# artlight_cornhole.net
KiCad netlist of a schematic drawn in EAGLE
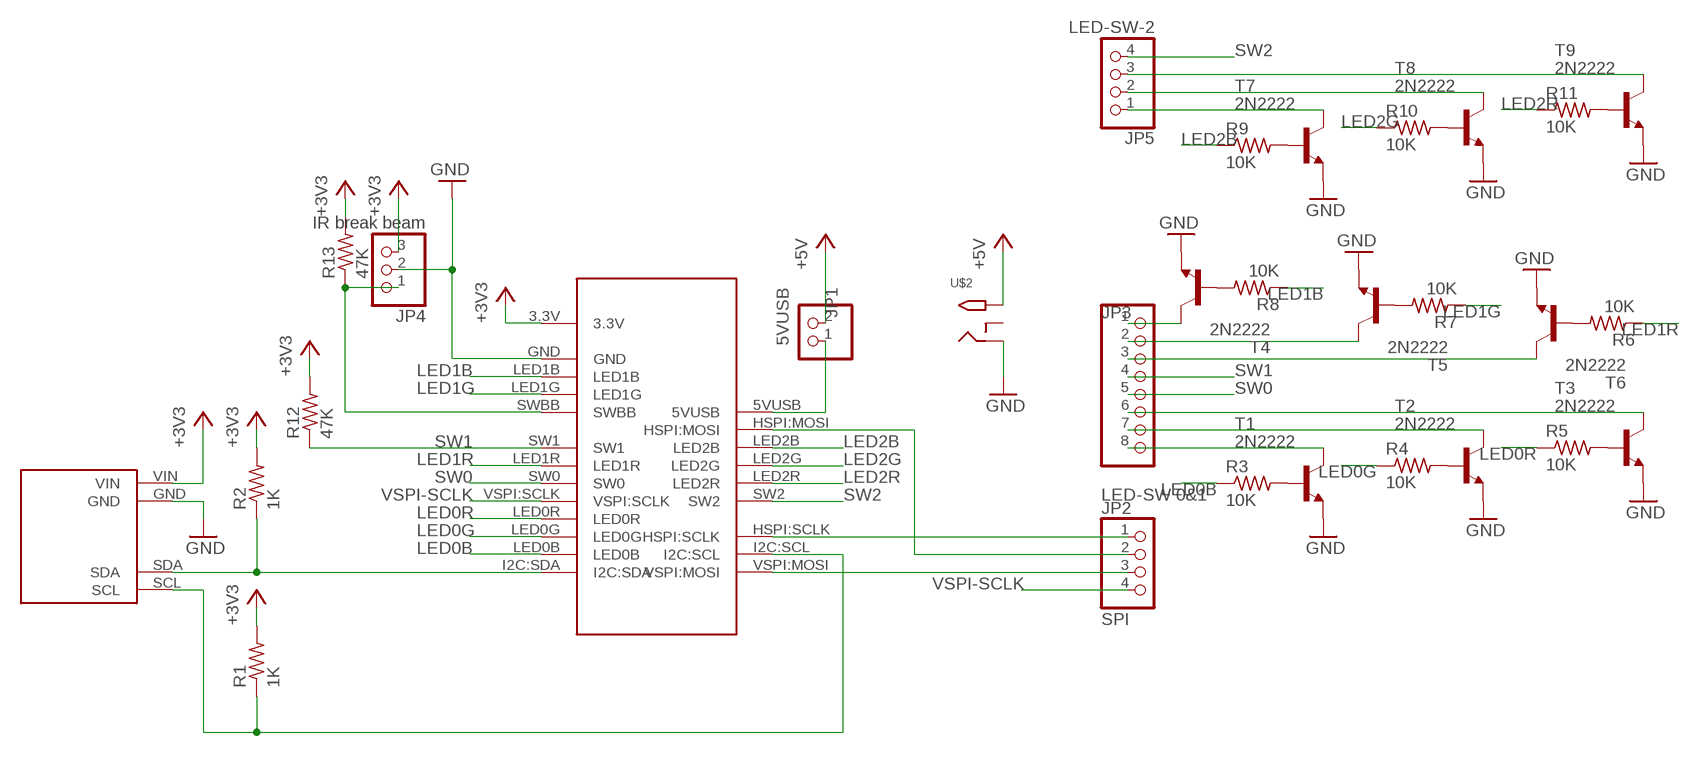
[diagram p0: schematic, sheet 1]

(export (version "E")
  (design (tool "Eeschema 10.0.6"))
  (components
    (comp (ref "JP1")
      (value "5VUSB")
      (footprint "eagle-import:1X02")
      (libsource (lib "eagle-import") (part "PINHD-1X2"))
    )
    (comp (ref "JP2")
      (value "SPI")
      (footprint "eagle-import:1X04")
      (libsource (lib "eagle-import") (part "PINHD-1X4"))
    )
    (comp (ref "JP3")
      (value "LED-SW 0&1")
      (footprint "eagle-import:1X08")
      (libsource (lib "eagle-import") (part "PINHD-1X8"))
    )
    (comp (ref "JP4")
      (value "IR break beam")
      (footprint "eagle-import:1X03")
      (libsource (lib "eagle-import") (part "PINHD-1X3"))
    )
    (comp (ref "JP5")
      (value "LED-SW-2")
      (footprint "eagle-import:1X04")
      (libsource (lib "eagle-import") (part "PINHD-1X4"))
    )
    (comp (ref "R1")
      (value "1K")
      (footprint "eagle-import:0204_7")
      (libsource (lib "eagle-import") (part "R-US_0204/7"))
    )
    (comp (ref "R2")
      (value "1K")
      (footprint "eagle-import:0204_7")
      (libsource (lib "eagle-import") (part "R-US_0204/7"))
    )
    (comp (ref "R3")
      (value "10K")
      (footprint "eagle-import:0204V")
      (libsource (lib "eagle-import") (part "R-US_0204/2V"))
    )
    (comp (ref "R4")
      (value "10K")
      (footprint "eagle-import:0204V")
      (libsource (lib "eagle-import") (part "R-US_0204/2V"))
    )
    (comp (ref "R5")
      (value "10K")
      (footprint "eagle-import:0204V")
      (libsource (lib "eagle-import") (part "R-US_0204/2V"))
    )
    (comp (ref "R6")
      (value "10K")
      (footprint "eagle-import:0204V")
      (libsource (lib "eagle-import") (part "R-US_0204/2V"))
    )
    (comp (ref "R7")
      (value "10K")
      (footprint "eagle-import:0204V")
      (libsource (lib "eagle-import") (part "R-US_0204/2V"))
    )
    (comp (ref "R8")
      (value "10K")
      (footprint "eagle-import:0204V")
      (libsource (lib "eagle-import") (part "R-US_0204/2V"))
    )
    (comp (ref "R9")
      (value "10K")
      (footprint "eagle-import:0204V")
      (libsource (lib "eagle-import") (part "R-US_0204/2V"))
    )
    (comp (ref "R10")
      (value "10K")
      (footprint "eagle-import:0204V")
      (libsource (lib "eagle-import") (part "R-US_0204/2V"))
    )
    (comp (ref "R11")
      (value "10K")
      (footprint "eagle-import:0204V")
      (libsource (lib "eagle-import") (part "R-US_0204/2V"))
    )
    (comp (ref "R12")
      (value "47K")
      (footprint "eagle-import:0204_7")
      (libsource (lib "eagle-import") (part "R-US_0204/7"))
    )
    (comp (ref "R13")
      (value "47K")
      (footprint "eagle-import:0204_7")
      (libsource (lib "eagle-import") (part "R-US_0204/7"))
    )
    (comp (ref "T1")
      (value "2N2222")
      (footprint "eagle-import:TO92-EBC-OVAL")
      (libsource (lib "eagle-import") (part "2N2222"))
    )
    (comp (ref "T2")
      (value "2N2222")
      (footprint "eagle-import:TO92-EBC-OVAL")
      (libsource (lib "eagle-import") (part "2N2222"))
    )
    (comp (ref "T3")
      (value "2N2222")
      (footprint "eagle-import:TO92-EBC-OVAL")
      (libsource (lib "eagle-import") (part "2N2222"))
    )
    (comp (ref "T4")
      (value "2N2222")
      (footprint "eagle-import:TO92-EBC-OVAL")
      (libsource (lib "eagle-import") (part "2N2222"))
    )
    (comp (ref "T5")
      (value "2N2222")
      (footprint "eagle-import:TO92-EBC-OVAL")
      (libsource (lib "eagle-import") (part "2N2222"))
    )
    (comp (ref "T6")
      (value "2N2222")
      (footprint "eagle-import:TO92-EBC-OVAL")
      (libsource (lib "eagle-import") (part "2N2222"))
    )
    (comp (ref "T7")
      (value "2N2222")
      (footprint "eagle-import:TO92-EBC-OVAL")
      (libsource (lib "eagle-import") (part "2N2222"))
    )
    (comp (ref "T8")
      (value "2N2222")
      (footprint "eagle-import:TO92-EBC-OVAL")
      (libsource (lib "eagle-import") (part "2N2222"))
    )
    (comp (ref "T9")
      (value "2N2222")
      (footprint "eagle-import:TO92-EBC-OVAL")
      (libsource (lib "eagle-import") (part "2N2222"))
    )
    (comp (ref "U$1")
      (value "HUZZAH32-ARTLIGHT.CORNHOLE")
      (footprint "eagle-import:FEATHERWING-ARTLIGHT.CORNHOLE")
      (libsource (lib "eagle-import") (part "HUZZAH32-ARTLIGHT.CORNHOLE"))
    )
    (comp (ref "U$2")
      (value "2.1MMJACKTHM")
      (footprint "eagle-import:PJ-102A")
      (libsource (lib "eagle-import") (part "2.1MMJACKTHM"))
    )
    (comp (ref "U$3")
      (value "TSL2561-ARTLIGHT")
      (footprint "eagle-import:TSL2561-ARTLIGHT")
      (libsource (lib "eagle-import") (part "TSL2561-ARTLIGHT"))
    )
  )
  (nets
    (net (code "1") (name "+3V3") (class "Default")
      (node (ref "JP4") (pin "3") (pinfunction "3_3") (pintype "passive"))
      (node (ref "R1") (pin "2") (pinfunction "2_2") (pintype "passive"))
      (node (ref "R12") (pin "2") (pinfunction "2_2") (pintype "passive"))
      (node (ref "R13") (pin "2") (pinfunction "2_2") (pintype "passive"))
      (node (ref "R2") (pin "2") (pinfunction "2_2") (pintype "passive"))
      (node (ref "U$1") (pin "3.3V") (pinfunction "3.3V_3.3V") (pintype "bidirectional"))
      (node (ref "U$3") (pin "VIN") (pinfunction "VIN_VIN") (pintype "bidirectional"))
    )
    (net (code "2") (name "+5V") (class "Default")
      (node (ref "JP1") (pin "2") (pinfunction "2_2") (pintype "passive"))
      (node (ref "U$2") (pin "TIP") (pinfunction "TIP_TIP") (pintype "bidirectional"))
    )
    (net (code "3") (name "/LED0B") (class "Default")
      (node (ref "R3") (pin "1") (pinfunction "1_1") (pintype "passive"))
      (node (ref "U$1") (pin "LED0B") (pinfunction "LED0B_LED0B") (pintype "bidirectional"))
    )
    (net (code "4") (name "/LED0G") (class "Default")
      (node (ref "R4") (pin "1") (pinfunction "1_1") (pintype "passive"))
      (node (ref "U$1") (pin "LED0G") (pinfunction "LED0G_LED0G") (pintype "bidirectional"))
    )
    (net (code "5") (name "/LED0R") (class "Default")
      (node (ref "R5") (pin "1") (pinfunction "1_1") (pintype "passive"))
      (node (ref "U$1") (pin "LED0R") (pinfunction "LED0R_LED0R") (pintype "bidirectional"))
    )
    (net (code "6") (name "/LED1B") (class "Default")
      (node (ref "R8") (pin "1") (pinfunction "1_1") (pintype "passive"))
      (node (ref "U$1") (pin "LED1B") (pinfunction "LED1B_LED1B") (pintype "bidirectional"))
    )
    (net (code "7") (name "/LED1G") (class "Default")
      (node (ref "R7") (pin "1") (pinfunction "1_1") (pintype "passive"))
      (node (ref "U$1") (pin "LED1G") (pinfunction "LED1G_LED1G") (pintype "bidirectional"))
    )
    (net (code "8") (name "/LED1R") (class "Default")
      (node (ref "R6") (pin "1") (pinfunction "1_1") (pintype "passive"))
      (node (ref "U$1") (pin "LED1R") (pinfunction "LED1R_LED1R") (pintype "bidirectional"))
    )
    (net (code "9") (name "/LED2B") (class "Default")
      (node (ref "R9") (pin "1") (pinfunction "1_1") (pintype "passive"))
      (node (ref "U$1") (pin "LED2B") (pinfunction "LED2B_LED2B") (pintype "bidirectional"))
    )
    (net (code "10") (name "/LED2G") (class "Default")
      (node (ref "R10") (pin "1") (pinfunction "1_1") (pintype "passive"))
      (node (ref "U$1") (pin "LED2G") (pinfunction "LED2G_LED2G") (pintype "bidirectional"))
    )
    (net (code "11") (name "/LED2R") (class "Default")
      (node (ref "R11") (pin "1") (pinfunction "1_1") (pintype "passive"))
      (node (ref "U$1") (pin "LED2R") (pinfunction "LED2R_LED2R") (pintype "bidirectional"))
    )
    (net (code "12") (name "/SW0") (class "Default")
      (node (ref "JP3") (pin "5") (pinfunction "5_5") (pintype "passive"))
      (node (ref "U$1") (pin "SW0") (pinfunction "SW0_SW0") (pintype "bidirectional"))
    )
    (net (code "13") (name "/SW1") (class "Default")
      (node (ref "JP3") (pin "4") (pinfunction "4_4") (pintype "passive"))
      (node (ref "R12") (pin "1") (pinfunction "1_1") (pintype "passive"))
      (node (ref "U$1") (pin "SW1") (pinfunction "SW1_SW1") (pintype "bidirectional"))
    )
    (net (code "14") (name "/SW2") (class "Default")
      (node (ref "JP5") (pin "4") (pinfunction "4_4") (pintype "passive"))
      (node (ref "U$1") (pin "SW2") (pinfunction "SW2_SW2") (pintype "bidirectional"))
    )
    (net (code "15") (name "/VSPI-SCLK") (class "Default")
      (node (ref "JP2") (pin "4") (pinfunction "4_4") (pintype "passive"))
      (node (ref "U$1") (pin "VSPI:SCLK") (pinfunction "VSPI:SCLK_VSPI:SCLK") (pintype "bidirectional"))
    )
    (net (code "16") (name "GND") (class "Default")
      (node (ref "JP4") (pin "2") (pinfunction "2_2") (pintype "passive"))
      (node (ref "T1") (pin "E") (pinfunction "E_E") (pintype "passive"))
      (node (ref "T2") (pin "E") (pinfunction "E_E") (pintype "passive"))
      (node (ref "T3") (pin "E") (pinfunction "E_E") (pintype "passive"))
      (node (ref "T4") (pin "E") (pinfunction "E_E") (pintype "passive"))
      (node (ref "T5") (pin "E") (pinfunction "E_E") (pintype "passive"))
      (node (ref "T6") (pin "E") (pinfunction "E_E") (pintype "passive"))
      (node (ref "T7") (pin "E") (pinfunction "E_E") (pintype "passive"))
      (node (ref "T8") (pin "E") (pinfunction "E_E") (pintype "passive"))
      (node (ref "T9") (pin "E") (pinfunction "E_E") (pintype "passive"))
      (node (ref "U$1") (pin "GND") (pinfunction "GND_GND") (pintype "bidirectional"))
      (node (ref "U$2") (pin "RING") (pinfunction "RING_RING") (pintype "bidirectional"))
      (node (ref "U$3") (pin "GND") (pinfunction "GND_GND") (pintype "bidirectional"))
    )
    (net (code "17") (name "Net-(JP1-Pad1)") (class "Default")
      (node (ref "JP1") (pin "1") (pinfunction "1_1") (pintype "passive"))
      (node (ref "U$1") (pin "5VUSB") (pinfunction "5VUSB_5VUSB") (pintype "bidirectional"))
    )
    (net (code "18") (name "Net-(JP2-Pad1)") (class "Default")
      (node (ref "JP2") (pin "1") (pinfunction "1_1") (pintype "passive"))
      (node (ref "U$1") (pin "HSPI:SCLK") (pinfunction "HSPI:SCLK_HSPI:SCLK") (pintype "bidirectional"))
    )
    (net (code "19") (name "Net-(JP2-Pad2)") (class "Default")
      (node (ref "JP2") (pin "2") (pinfunction "2_2") (pintype "passive"))
      (node (ref "U$1") (pin "HSPI:MOSI") (pinfunction "HSPI:MOSI_HSPI:MOSI") (pintype "bidirectional"))
    )
    (net (code "20") (name "Net-(JP2-Pad3)") (class "Default")
      (node (ref "JP2") (pin "3") (pinfunction "3_3") (pintype "passive"))
      (node (ref "U$1") (pin "VSPI:MOSI") (pinfunction "VSPI:MOSI_VSPI:MOSI") (pintype "bidirectional"))
    )
    (net (code "21") (name "Net-(JP3-Pad1)") (class "Default")
      (node (ref "JP3") (pin "1") (pinfunction "1_1") (pintype "passive"))
      (node (ref "T4") (pin "C") (pinfunction "C_C") (pintype "passive"))
    )
    (net (code "22") (name "Net-(JP3-Pad2)") (class "Default")
      (node (ref "JP3") (pin "2") (pinfunction "2_2") (pintype "passive"))
      (node (ref "T5") (pin "C") (pinfunction "C_C") (pintype "passive"))
    )
    (net (code "23") (name "Net-(JP3-Pad3)") (class "Default")
      (node (ref "JP3") (pin "3") (pinfunction "3_3") (pintype "passive"))
      (node (ref "T6") (pin "C") (pinfunction "C_C") (pintype "passive"))
    )
    (net (code "24") (name "Net-(JP3-Pad6)") (class "Default")
      (node (ref "JP3") (pin "6") (pinfunction "6_6") (pintype "passive"))
      (node (ref "T3") (pin "C") (pinfunction "C_C") (pintype "passive"))
    )
    (net (code "25") (name "Net-(JP3-Pad7)") (class "Default")
      (node (ref "JP3") (pin "7") (pinfunction "7_7") (pintype "passive"))
      (node (ref "T2") (pin "C") (pinfunction "C_C") (pintype "passive"))
    )
    (net (code "26") (name "Net-(JP3-Pad8)") (class "Default")
      (node (ref "JP3") (pin "8") (pinfunction "8_8") (pintype "passive"))
      (node (ref "T1") (pin "C") (pinfunction "C_C") (pintype "passive"))
    )
    (net (code "27") (name "Net-(JP4-Pad1)") (class "Default")
      (node (ref "JP4") (pin "1") (pinfunction "1_1") (pintype "passive"))
      (node (ref "R13") (pin "1") (pinfunction "1_1") (pintype "passive"))
      (node (ref "U$1") (pin "SWBB") (pinfunction "SWBB_SWBB") (pintype "bidirectional"))
    )
    (net (code "28") (name "Net-(JP5-Pad1)") (class "Default")
      (node (ref "JP5") (pin "1") (pinfunction "1_1") (pintype "passive"))
      (node (ref "T7") (pin "C") (pinfunction "C_C") (pintype "passive"))
    )
    (net (code "29") (name "Net-(JP5-Pad2)") (class "Default")
      (node (ref "JP5") (pin "2") (pinfunction "2_2") (pintype "passive"))
      (node (ref "T8") (pin "C") (pinfunction "C_C") (pintype "passive"))
    )
    (net (code "30") (name "Net-(JP5-Pad3)") (class "Default")
      (node (ref "JP5") (pin "3") (pinfunction "3_3") (pintype "passive"))
      (node (ref "T9") (pin "C") (pinfunction "C_C") (pintype "passive"))
    )
    (net (code "31") (name "Net-(R1-Pad1)") (class "Default")
      (node (ref "R1") (pin "1") (pinfunction "1_1") (pintype "passive"))
      (node (ref "U$1") (pin "I2C:SCL") (pinfunction "I2C:SCL_I2C:SCL") (pintype "bidirectional"))
      (node (ref "U$3") (pin "SCL") (pinfunction "SCL_SCL") (pintype "bidirectional"))
    )
    (net (code "32") (name "Net-(R2-Pad1)") (class "Default")
      (node (ref "R2") (pin "1") (pinfunction "1_1") (pintype "passive"))
      (node (ref "U$1") (pin "I2C:SDA") (pinfunction "I2C:SDA_I2C:SDA") (pintype "bidirectional"))
      (node (ref "U$3") (pin "SDA") (pinfunction "SDA_SDA") (pintype "bidirectional"))
    )
    (net (code "33") (name "Net-(R3-Pad2)") (class "Default")
      (node (ref "R3") (pin "2") (pinfunction "2_2") (pintype "passive"))
      (node (ref "T1") (pin "B") (pinfunction "B_B") (pintype "passive"))
    )
    (net (code "34") (name "Net-(R4-Pad2)") (class "Default")
      (node (ref "R4") (pin "2") (pinfunction "2_2") (pintype "passive"))
      (node (ref "T2") (pin "B") (pinfunction "B_B") (pintype "passive"))
    )
    (net (code "35") (name "Net-(R5-Pad2)") (class "Default")
      (node (ref "R5") (pin "2") (pinfunction "2_2") (pintype "passive"))
      (node (ref "T3") (pin "B") (pinfunction "B_B") (pintype "passive"))
    )
    (net (code "36") (name "Net-(R6-Pad2)") (class "Default")
      (node (ref "R6") (pin "2") (pinfunction "2_2") (pintype "passive"))
      (node (ref "T6") (pin "B") (pinfunction "B_B") (pintype "passive"))
    )
    (net (code "37") (name "Net-(R7-Pad2)") (class "Default")
      (node (ref "R7") (pin "2") (pinfunction "2_2") (pintype "passive"))
      (node (ref "T5") (pin "B") (pinfunction "B_B") (pintype "passive"))
    )
    (net (code "38") (name "Net-(R8-Pad2)") (class "Default")
      (node (ref "R8") (pin "2") (pinfunction "2_2") (pintype "passive"))
      (node (ref "T4") (pin "B") (pinfunction "B_B") (pintype "passive"))
    )
    (net (code "39") (name "Net-(R9-Pad2)") (class "Default")
      (node (ref "R9") (pin "2") (pinfunction "2_2") (pintype "passive"))
      (node (ref "T7") (pin "B") (pinfunction "B_B") (pintype "passive"))
    )
    (net (code "40") (name "Net-(R10-Pad2)") (class "Default")
      (node (ref "R10") (pin "2") (pinfunction "2_2") (pintype "passive"))
      (node (ref "T8") (pin "B") (pinfunction "B_B") (pintype "passive"))
    )
    (net (code "41") (name "Net-(R11-Pad2)") (class "Default")
      (node (ref "R11") (pin "2") (pinfunction "2_2") (pintype "passive"))
      (node (ref "T9") (pin "B") (pinfunction "B_B") (pintype "passive"))
    )
    (net (code "42") (name "unconnected-(U$2-PadRING_SW)") (class "Default")
      (node (ref "U$2") (pin "RING_SW") (pinfunction "RING_SW_RING_SW") (pintype "bidirectional"))
    )
  )
)
